# PCB-BI8-SE-C201.net
KiCad netlist of a schematic drawn in EAGLE
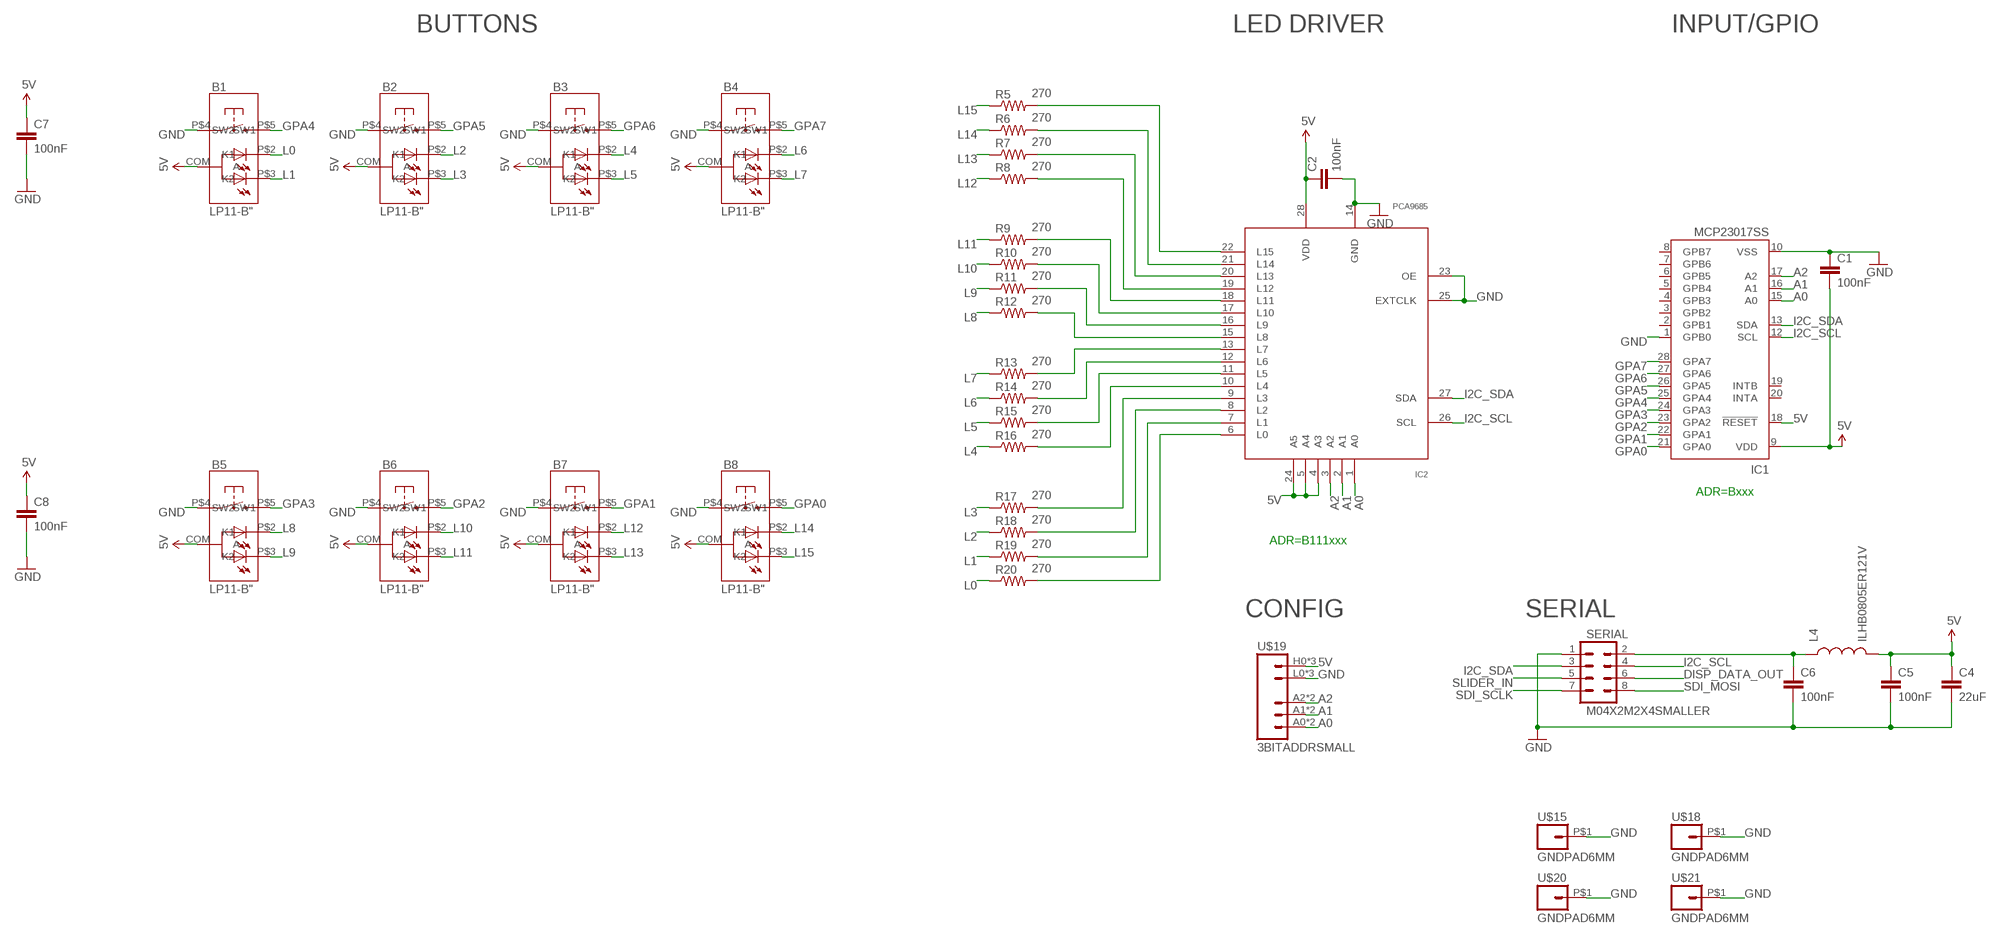
[diagram p0: schematic, sheet 1]

(export (version "E")
  (design (tool "Eeschema 10.0.6"))
  (components
    (comp (ref "B1")
      (value "LP11-B\"")
      (footprint "eagle-import:LP11")
      (libsource (lib "eagle-import") (part "LP11-B{dblquote}"))
    )
    (comp (ref "B2")
      (value "LP11-B\"")
      (footprint "eagle-import:LP11")
      (libsource (lib "eagle-import") (part "LP11-B{dblquote}"))
    )
    (comp (ref "B3")
      (value "LP11-B\"")
      (footprint "eagle-import:LP11")
      (libsource (lib "eagle-import") (part "LP11-B{dblquote}"))
    )
    (comp (ref "B4")
      (value "LP11-B\"")
      (footprint "eagle-import:LP11")
      (libsource (lib "eagle-import") (part "LP11-B{dblquote}"))
    )
    (comp (ref "B5")
      (value "LP11-B\"")
      (footprint "eagle-import:LP11")
      (libsource (lib "eagle-import") (part "LP11-B{dblquote}"))
    )
    (comp (ref "B6")
      (value "LP11-B\"")
      (footprint "eagle-import:LP11")
      (libsource (lib "eagle-import") (part "LP11-B{dblquote}"))
    )
    (comp (ref "B7")
      (value "LP11-B\"")
      (footprint "eagle-import:LP11")
      (libsource (lib "eagle-import") (part "LP11-B{dblquote}"))
    )
    (comp (ref "B8")
      (value "LP11-B\"")
      (footprint "eagle-import:LP11")
      (libsource (lib "eagle-import") (part "LP11-B{dblquote}"))
    )
    (comp (ref "C1")
      (value "100nF")
      (footprint "eagle-import:0603-CAP")
      (libsource (lib "eagle-import") (part "CAP0603-CAP"))
    )
    (comp (ref "C2")
      (value "100nF")
      (footprint "eagle-import:0603-CAP")
      (libsource (lib "eagle-import") (part "CAP0603-CAP"))
    )
    (comp (ref "C4")
      (value "22uF")
      (footprint "eagle-import:0805")
      (libsource (lib "eagle-import") (part "CAP0805"))
    )
    (comp (ref "C5")
      (value "100nF")
      (footprint "eagle-import:0603-CAP")
      (libsource (lib "eagle-import") (part "CAP0603-CAP"))
    )
    (comp (ref "C6")
      (value "100nF")
      (footprint "eagle-import:0603-CAP")
      (libsource (lib "eagle-import") (part "CAP0603-CAP"))
    )
    (comp (ref "C7")
      (value "100nF")
      (footprint "eagle-import:0603-CAP")
      (libsource (lib "eagle-import") (part "CAP0603-CAP"))
    )
    (comp (ref "C8")
      (value "100nF")
      (footprint "eagle-import:0603-CAP")
      (libsource (lib "eagle-import") (part "CAP0603-CAP"))
    )
    (comp (ref "IC1")
      (value "MCP23017SS")
      (footprint "eagle-import:SSOP28")
      (fields
        (field (name "MF") "MICROCHIP")
        (field (name "MPN") "MCP23017-E/SS")
        (field (name "MPN_1") "MCP23017-E/SS")
        (field (name "OC_FARNELL") "1467674")
        (field (name "OC_NEWARK") "31K2960")
      )
      (libsource (lib "eagle-import") (part "MCP23017SS"))
    )
    (comp (ref "IC2")
      (value "PCA9685")
      (footprint "eagle-import:TSSOP28")
      (libsource (lib "eagle-import") (part "PCA9685"))
    )
    (comp (ref "L4")
      (value "ILHB0805ER121V")
      (footprint "eagle-import:0805")
      (libsource (lib "eagle-import") (part "INDUCTOR0805"))
    )
    (comp (ref "R5")
      (value "270")
      (footprint "eagle-import:0603-RES")
      (libsource (lib "eagle-import") (part "RESISTOR0603-RES"))
    )
    (comp (ref "R6")
      (value "270")
      (footprint "eagle-import:0603-RES")
      (libsource (lib "eagle-import") (part "RESISTOR0603-RES"))
    )
    (comp (ref "R7")
      (value "270")
      (footprint "eagle-import:0603-RES")
      (libsource (lib "eagle-import") (part "RESISTOR0603-RES"))
    )
    (comp (ref "R8")
      (value "270")
      (footprint "eagle-import:0603-RES")
      (libsource (lib "eagle-import") (part "RESISTOR0603-RES"))
    )
    (comp (ref "R9")
      (value "270")
      (footprint "eagle-import:0603-RES")
      (libsource (lib "eagle-import") (part "RESISTOR0603-RES"))
    )
    (comp (ref "R10")
      (value "270")
      (footprint "eagle-import:0603-RES")
      (libsource (lib "eagle-import") (part "RESISTOR0603-RES"))
    )
    (comp (ref "R11")
      (value "270")
      (footprint "eagle-import:0603-RES")
      (libsource (lib "eagle-import") (part "RESISTOR0603-RES"))
    )
    (comp (ref "R12")
      (value "270")
      (footprint "eagle-import:0603-RES")
      (libsource (lib "eagle-import") (part "RESISTOR0603-RES"))
    )
    (comp (ref "R13")
      (value "270")
      (footprint "eagle-import:0603-RES")
      (libsource (lib "eagle-import") (part "RESISTOR0603-RES"))
    )
    (comp (ref "R14")
      (value "270")
      (footprint "eagle-import:0603-RES")
      (libsource (lib "eagle-import") (part "RESISTOR0603-RES"))
    )
    (comp (ref "R15")
      (value "270")
      (footprint "eagle-import:0603-RES")
      (libsource (lib "eagle-import") (part "RESISTOR0603-RES"))
    )
    (comp (ref "R16")
      (value "270")
      (footprint "eagle-import:0603-RES")
      (libsource (lib "eagle-import") (part "RESISTOR0603-RES"))
    )
    (comp (ref "R17")
      (value "270")
      (footprint "eagle-import:0603-RES")
      (libsource (lib "eagle-import") (part "RESISTOR0603-RES"))
    )
    (comp (ref "R18")
      (value "270")
      (footprint "eagle-import:0603-RES")
      (libsource (lib "eagle-import") (part "RESISTOR0603-RES"))
    )
    (comp (ref "R19")
      (value "270")
      (footprint "eagle-import:0603-RES")
      (libsource (lib "eagle-import") (part "RESISTOR0603-RES"))
    )
    (comp (ref "R20")
      (value "270")
      (footprint "eagle-import:0603-RES")
      (libsource (lib "eagle-import") (part "RESISTOR0603-RES"))
    )
    (comp (ref "SERIAL")
      (value "M04X2M2X4SMALLER")
      (footprint "eagle-import:M2X4SMALLER")
      (libsource (lib "eagle-import") (part "M04X2M2X4SMALLER"))
    )
    (comp (ref "U$15")
      (value "GNDPAD6MM")
      (footprint "eagle-import:3.2MMPAD6MM")
      (libsource (lib "eagle-import") (part "GNDPAD6MM"))
    )
    (comp (ref "U$18")
      (value "GNDPAD6MM")
      (footprint "eagle-import:3.2MMPAD6MM")
      (libsource (lib "eagle-import") (part "GNDPAD6MM"))
    )
    (comp (ref "U$19")
      (value "3BITADDRSMALL")
      (footprint "eagle-import:3BITADDR_SMALL")
      (libsource (lib "eagle-import") (part "3BITADDRSMALL"))
    )
    (comp (ref "U$20")
      (value "GNDPAD6MM")
      (footprint "eagle-import:3.2MMPAD6MM")
      (libsource (lib "eagle-import") (part "GNDPAD6MM"))
    )
    (comp (ref "U$21")
      (value "GNDPAD6MM")
      (footprint "eagle-import:3.2MMPAD6MM")
      (libsource (lib "eagle-import") (part "GNDPAD6MM"))
    )
  )
  (nets
    (net (code "1") (name "/A0") (class "Default")
      (node (ref "IC1") (pin "15") (pinfunction "A0_15") (pintype "input"))
      (node (ref "IC2") (pin "1") (pinfunction "A0_1") (pintype "input"))
      (node (ref "U$19") (pin "A0") (pinfunction "A0_A0") (pintype "passive"))
      (node (ref "U$19") (pin "AS0") (pinfunction "A0_AS0") (pintype "passive"))
    )
    (net (code "2") (name "/A1") (class "Default")
      (node (ref "IC1") (pin "16") (pinfunction "A1_16") (pintype "input"))
      (node (ref "IC2") (pin "2") (pinfunction "A1_2") (pintype "input"))
      (node (ref "U$19") (pin "A1") (pinfunction "A1_A1") (pintype "passive"))
      (node (ref "U$19") (pin "AS1") (pinfunction "A1_AS1") (pintype "passive"))
    )
    (net (code "3") (name "/A2") (class "Default")
      (node (ref "IC1") (pin "17") (pinfunction "A2_17") (pintype "input"))
      (node (ref "IC2") (pin "3") (pinfunction "A2_3") (pintype "input"))
      (node (ref "U$19") (pin "A2") (pinfunction "A2_A2") (pintype "passive"))
      (node (ref "U$19") (pin "AS2") (pinfunction "A2_AS2") (pintype "passive"))
    )
    (net (code "4") (name "/DISP_DATA_OUT") (class "Default")
      (node (ref "SERIAL") (pin "6") (pinfunction "6_6") (pintype "passive"))
    )
    (net (code "5") (name "/GPA0") (class "Default")
      (node (ref "B8") (pin "P$5") (pinfunction "SW2_P$5") (pintype "bidirectional"))
      (node (ref "IC1") (pin "21") (pinfunction "GPA0_21") (pintype "bidirectional"))
    )
    (net (code "6") (name "/GPA1") (class "Default")
      (node (ref "B7") (pin "P$5") (pinfunction "SW2_P$5") (pintype "bidirectional"))
      (node (ref "IC1") (pin "22") (pinfunction "GPA1_22") (pintype "bidirectional"))
    )
    (net (code "7") (name "/GPA2") (class "Default")
      (node (ref "B6") (pin "P$5") (pinfunction "SW2_P$5") (pintype "bidirectional"))
      (node (ref "IC1") (pin "23") (pinfunction "GPA2_23") (pintype "bidirectional"))
    )
    (net (code "8") (name "/GPA3") (class "Default")
      (node (ref "B5") (pin "P$5") (pinfunction "SW2_P$5") (pintype "bidirectional"))
      (node (ref "IC1") (pin "24") (pinfunction "GPA3_24") (pintype "bidirectional"))
    )
    (net (code "9") (name "/GPA4") (class "Default")
      (node (ref "B1") (pin "P$5") (pinfunction "SW2_P$5") (pintype "bidirectional"))
      (node (ref "IC1") (pin "25") (pinfunction "GPA4_25") (pintype "bidirectional"))
    )
    (net (code "10") (name "/GPA5") (class "Default")
      (node (ref "B2") (pin "P$5") (pinfunction "SW2_P$5") (pintype "bidirectional"))
      (node (ref "IC1") (pin "26") (pinfunction "GPA5_26") (pintype "bidirectional"))
    )
    (net (code "11") (name "/GPA6") (class "Default")
      (node (ref "B3") (pin "P$5") (pinfunction "SW2_P$5") (pintype "bidirectional"))
      (node (ref "IC1") (pin "27") (pinfunction "GPA6_27") (pintype "bidirectional"))
    )
    (net (code "12") (name "/GPA7") (class "Default")
      (node (ref "B4") (pin "P$5") (pinfunction "SW2_P$5") (pintype "bidirectional"))
      (node (ref "IC1") (pin "28") (pinfunction "GPA7_28") (pintype "bidirectional"))
    )
    (net (code "13") (name "/I2C_SCL") (class "Default")
      (node (ref "IC1") (pin "12") (pinfunction "SCL_12") (pintype "input"))
      (node (ref "IC2") (pin "26") (pinfunction "SCL_26") (pintype "input"))
      (node (ref "SERIAL") (pin "4") (pinfunction "4_4") (pintype "passive"))
    )
    (net (code "14") (name "/I2C_SDA") (class "Default")
      (node (ref "IC1") (pin "13") (pinfunction "SDA_13") (pintype "bidirectional"))
      (node (ref "IC2") (pin "27") (pinfunction "SDA_27") (pintype "input"))
      (node (ref "SERIAL") (pin "3") (pinfunction "3_3") (pintype "passive"))
    )
    (net (code "15") (name "/L0") (class "Default")
      (node (ref "B1") (pin "P$2") (pinfunction "K1_P$2") (pintype "bidirectional"))
      (node (ref "R20") (pin "1") (pinfunction "1_1") (pintype "passive"))
    )
    (net (code "16") (name "/L1") (class "Default")
      (node (ref "B1") (pin "P$3") (pinfunction "K2_P$3") (pintype "bidirectional"))
      (node (ref "R19") (pin "1") (pinfunction "1_1") (pintype "passive"))
    )
    (net (code "17") (name "/L2") (class "Default")
      (node (ref "B2") (pin "P$2") (pinfunction "K1_P$2") (pintype "bidirectional"))
      (node (ref "R18") (pin "1") (pinfunction "1_1") (pintype "passive"))
    )
    (net (code "18") (name "/L3") (class "Default")
      (node (ref "B2") (pin "P$3") (pinfunction "K2_P$3") (pintype "bidirectional"))
      (node (ref "R17") (pin "1") (pinfunction "1_1") (pintype "passive"))
    )
    (net (code "19") (name "/L4") (class "Default")
      (node (ref "B3") (pin "P$2") (pinfunction "K1_P$2") (pintype "bidirectional"))
      (node (ref "R16") (pin "1") (pinfunction "1_1") (pintype "passive"))
    )
    (net (code "20") (name "/L5") (class "Default")
      (node (ref "B3") (pin "P$3") (pinfunction "K2_P$3") (pintype "bidirectional"))
      (node (ref "R15") (pin "1") (pinfunction "1_1") (pintype "passive"))
    )
    (net (code "21") (name "/L6") (class "Default")
      (node (ref "B4") (pin "P$2") (pinfunction "K1_P$2") (pintype "bidirectional"))
      (node (ref "R14") (pin "1") (pinfunction "1_1") (pintype "passive"))
    )
    (net (code "22") (name "/L7") (class "Default")
      (node (ref "B4") (pin "P$3") (pinfunction "K2_P$3") (pintype "bidirectional"))
      (node (ref "R13") (pin "1") (pinfunction "1_1") (pintype "passive"))
    )
    (net (code "23") (name "/L8") (class "Default")
      (node (ref "B5") (pin "P$2") (pinfunction "K1_P$2") (pintype "bidirectional"))
      (node (ref "R12") (pin "1") (pinfunction "1_1") (pintype "passive"))
    )
    (net (code "24") (name "/L9") (class "Default")
      (node (ref "B5") (pin "P$3") (pinfunction "K2_P$3") (pintype "bidirectional"))
      (node (ref "R11") (pin "1") (pinfunction "1_1") (pintype "passive"))
    )
    (net (code "25") (name "/L10") (class "Default")
      (node (ref "B6") (pin "P$2") (pinfunction "K1_P$2") (pintype "bidirectional"))
      (node (ref "R10") (pin "1") (pinfunction "1_1") (pintype "passive"))
    )
    (net (code "26") (name "/L11") (class "Default")
      (node (ref "B6") (pin "P$3") (pinfunction "K2_P$3") (pintype "bidirectional"))
      (node (ref "R9") (pin "1") (pinfunction "1_1") (pintype "passive"))
    )
    (net (code "27") (name "/L12") (class "Default")
      (node (ref "B7") (pin "P$2") (pinfunction "K1_P$2") (pintype "bidirectional"))
      (node (ref "R8") (pin "1") (pinfunction "1_1") (pintype "passive"))
    )
    (net (code "28") (name "/L13") (class "Default")
      (node (ref "B7") (pin "P$3") (pinfunction "K2_P$3") (pintype "bidirectional"))
      (node (ref "R7") (pin "1") (pinfunction "1_1") (pintype "passive"))
    )
    (net (code "29") (name "/L14") (class "Default")
      (node (ref "B8") (pin "P$2") (pinfunction "K1_P$2") (pintype "bidirectional"))
      (node (ref "R6") (pin "1") (pinfunction "1_1") (pintype "passive"))
    )
    (net (code "30") (name "/L15") (class "Default")
      (node (ref "B8") (pin "P$3") (pinfunction "K2_P$3") (pintype "bidirectional"))
      (node (ref "R5") (pin "1") (pinfunction "1_1") (pintype "passive"))
    )
    (net (code "31") (name "/SDI_MOSI") (class "Default")
      (node (ref "SERIAL") (pin "8") (pinfunction "8_8") (pintype "passive"))
    )
    (net (code "32") (name "/SDI_SCLK") (class "Default")
      (node (ref "SERIAL") (pin "7") (pinfunction "7_7") (pintype "passive"))
    )
    (net (code "33") (name "/SLIDER_IN") (class "Default")
      (node (ref "SERIAL") (pin "5") (pinfunction "5_5") (pintype "passive"))
    )
    (net (code "34") (name "5V") (class "Default")
      (node (ref "B1") (pin "COM") (pinfunction "A_COM") (pintype "bidirectional"))
      (node (ref "B2") (pin "COM") (pinfunction "A_COM") (pintype "bidirectional"))
      (node (ref "B3") (pin "COM") (pinfunction "A_COM") (pintype "bidirectional"))
      (node (ref "B4") (pin "COM") (pinfunction "A_COM") (pintype "bidirectional"))
      (node (ref "B5") (pin "COM") (pinfunction "A_COM") (pintype "bidirectional"))
      (node (ref "B6") (pin "COM") (pinfunction "A_COM") (pintype "bidirectional"))
      (node (ref "B7") (pin "COM") (pinfunction "A_COM") (pintype "bidirectional"))
      (node (ref "B8") (pin "COM") (pinfunction "A_COM") (pintype "bidirectional"))
      (node (ref "C1") (pin "2") (pinfunction "2_2") (pintype "passive"))
      (node (ref "C2") (pin "1") (pinfunction "1_1") (pintype "passive"))
      (node (ref "C4") (pin "1") (pinfunction "1_1") (pintype "passive"))
      (node (ref "C5") (pin "1") (pinfunction "1_1") (pintype "passive"))
      (node (ref "C7") (pin "1") (pinfunction "1_1") (pintype "passive"))
      (node (ref "C8") (pin "1") (pinfunction "1_1") (pintype "passive"))
      (node (ref "IC1") (pin "18") (pinfunction "~{RESET}_18") (pintype "input"))
      (node (ref "IC1") (pin "9") (pinfunction "VDD_9") (pintype "power_in"))
      (node (ref "IC2") (pin "24") (pinfunction "A5_24") (pintype "input"))
      (node (ref "IC2") (pin "28") (pinfunction "VDD_28") (pintype "power_in"))
      (node (ref "IC2") (pin "4") (pinfunction "A3_4") (pintype "input"))
      (node (ref "IC2") (pin "5") (pinfunction "A4_5") (pintype "input"))
      (node (ref "L4") (pin "2") (pinfunction "2_2") (pintype "passive"))
      (node (ref "U$19") (pin "H0") (pinfunction "VCC_H0") (pintype "passive"))
      (node (ref "U$19") (pin "H1") (pinfunction "VCC_H1") (pintype "passive"))
      (node (ref "U$19") (pin "H2") (pinfunction "VCC_H2") (pintype "passive"))
    )
    (net (code "35") (name "GND") (class "Default")
      (node (ref "B1") (pin "P$4") (pinfunction "SW1_P$4") (pintype "bidirectional"))
      (node (ref "B2") (pin "P$4") (pinfunction "SW1_P$4") (pintype "bidirectional"))
      (node (ref "B3") (pin "P$4") (pinfunction "SW1_P$4") (pintype "bidirectional"))
      (node (ref "B4") (pin "P$4") (pinfunction "SW1_P$4") (pintype "bidirectional"))
      (node (ref "B5") (pin "P$4") (pinfunction "SW1_P$4") (pintype "bidirectional"))
      (node (ref "B6") (pin "P$4") (pinfunction "SW1_P$4") (pintype "bidirectional"))
      (node (ref "B7") (pin "P$4") (pinfunction "SW1_P$4") (pintype "bidirectional"))
      (node (ref "B8") (pin "P$4") (pinfunction "SW1_P$4") (pintype "bidirectional"))
      (node (ref "C1") (pin "1") (pinfunction "1_1") (pintype "passive"))
      (node (ref "C2") (pin "2") (pinfunction "2_2") (pintype "passive"))
      (node (ref "C4") (pin "2") (pinfunction "2_2") (pintype "passive"))
      (node (ref "C5") (pin "2") (pinfunction "2_2") (pintype "passive"))
      (node (ref "C6") (pin "2") (pinfunction "2_2") (pintype "passive"))
      (node (ref "C7") (pin "2") (pinfunction "2_2") (pintype "passive"))
      (node (ref "C8") (pin "2") (pinfunction "2_2") (pintype "passive"))
      (node (ref "IC1") (pin "1") (pinfunction "GPB0_1") (pintype "bidirectional"))
      (node (ref "IC1") (pin "10") (pinfunction "VSS_10") (pintype "power_in"))
      (node (ref "IC2") (pin "14") (pinfunction "GND_14") (pintype "power_in"))
      (node (ref "IC2") (pin "23") (pinfunction "OE_23") (pintype "input"))
      (node (ref "IC2") (pin "25") (pinfunction "EXTCLK_25") (pintype "input"))
      (node (ref "SERIAL") (pin "1") (pinfunction "1_1") (pintype "passive"))
      (node (ref "U$15") (pin "P$1") (pinfunction "1_P$1") (pintype "passive"))
      (node (ref "U$18") (pin "P$1") (pinfunction "1_P$1") (pintype "passive"))
      (node (ref "U$19") (pin "L0") (pinfunction "GND_L0") (pintype "passive"))
      (node (ref "U$19") (pin "L1") (pinfunction "GND_L1") (pintype "passive"))
      (node (ref "U$19") (pin "L2") (pinfunction "GND_L2") (pintype "passive"))
      (node (ref "U$20") (pin "P$1") (pinfunction "1_P$1") (pintype "passive"))
      (node (ref "U$21") (pin "P$1") (pinfunction "1_P$1") (pintype "passive"))
    )
    (net (code "36") (name "Net-(C6-Pad1)") (class "Default")
      (node (ref "C6") (pin "1") (pinfunction "1_1") (pintype "passive"))
      (node (ref "L4") (pin "1") (pinfunction "1_1") (pintype "passive"))
      (node (ref "SERIAL") (pin "2") (pinfunction "2_2") (pintype "passive"))
    )
    (net (code "37") (name "Net-(IC2-L0)") (class "Default")
      (node (ref "IC2") (pin "6") (pinfunction "L0_6") (pintype "output"))
      (node (ref "R20") (pin "2") (pinfunction "2_2") (pintype "passive"))
    )
    (net (code "38") (name "Net-(IC2-L1)") (class "Default")
      (node (ref "IC2") (pin "7") (pinfunction "L1_7") (pintype "output"))
      (node (ref "R19") (pin "2") (pinfunction "2_2") (pintype "passive"))
    )
    (net (code "39") (name "Net-(IC2-L2)") (class "Default")
      (node (ref "IC2") (pin "8") (pinfunction "L2_8") (pintype "output"))
      (node (ref "R18") (pin "2") (pinfunction "2_2") (pintype "passive"))
    )
    (net (code "40") (name "Net-(IC2-L3)") (class "Default")
      (node (ref "IC2") (pin "9") (pinfunction "L3_9") (pintype "output"))
      (node (ref "R17") (pin "2") (pinfunction "2_2") (pintype "passive"))
    )
    (net (code "41") (name "Net-(IC2-L4)") (class "Default")
      (node (ref "IC2") (pin "10") (pinfunction "L4_10") (pintype "output"))
      (node (ref "R16") (pin "2") (pinfunction "2_2") (pintype "passive"))
    )
    (net (code "42") (name "Net-(IC2-L5)") (class "Default")
      (node (ref "IC2") (pin "11") (pinfunction "L5_11") (pintype "output"))
      (node (ref "R15") (pin "2") (pinfunction "2_2") (pintype "passive"))
    )
    (net (code "43") (name "Net-(IC2-L6)") (class "Default")
      (node (ref "IC2") (pin "12") (pinfunction "L6_12") (pintype "output"))
      (node (ref "R14") (pin "2") (pinfunction "2_2") (pintype "passive"))
    )
    (net (code "44") (name "Net-(IC2-L7)") (class "Default")
      (node (ref "IC2") (pin "13") (pinfunction "L7_13") (pintype "output"))
      (node (ref "R13") (pin "2") (pinfunction "2_2") (pintype "passive"))
    )
    (net (code "45") (name "Net-(IC2-L8)") (class "Default")
      (node (ref "IC2") (pin "15") (pinfunction "L8_15") (pintype "output"))
      (node (ref "R12") (pin "2") (pinfunction "2_2") (pintype "passive"))
    )
    (net (code "46") (name "Net-(IC2-L9)") (class "Default")
      (node (ref "IC2") (pin "16") (pinfunction "L9_16") (pintype "output"))
      (node (ref "R11") (pin "2") (pinfunction "2_2") (pintype "passive"))
    )
    (net (code "47") (name "Net-(IC2-L10)") (class "Default")
      (node (ref "IC2") (pin "17") (pinfunction "L10_17") (pintype "output"))
      (node (ref "R10") (pin "2") (pinfunction "2_2") (pintype "passive"))
    )
    (net (code "48") (name "Net-(IC2-L11)") (class "Default")
      (node (ref "IC2") (pin "18") (pinfunction "L11_18") (pintype "output"))
      (node (ref "R9") (pin "2") (pinfunction "2_2") (pintype "passive"))
    )
    (net (code "49") (name "Net-(IC2-L12)") (class "Default")
      (node (ref "IC2") (pin "19") (pinfunction "L12_19") (pintype "output"))
      (node (ref "R8") (pin "2") (pinfunction "2_2") (pintype "passive"))
    )
    (net (code "50") (name "Net-(IC2-L13)") (class "Default")
      (node (ref "IC2") (pin "20") (pinfunction "L13_20") (pintype "output"))
      (node (ref "R7") (pin "2") (pinfunction "2_2") (pintype "passive"))
    )
    (net (code "51") (name "Net-(IC2-L14)") (class "Default")
      (node (ref "IC2") (pin "21") (pinfunction "L14_21") (pintype "output"))
      (node (ref "R6") (pin "2") (pinfunction "2_2") (pintype "passive"))
    )
    (net (code "52") (name "Net-(IC2-L15)") (class "Default")
      (node (ref "IC2") (pin "22") (pinfunction "L15_22") (pintype "output"))
      (node (ref "R5") (pin "2") (pinfunction "2_2") (pintype "passive"))
    )
    (net (code "53") (name "unconnected-(IC1-GPB1-Pad2)") (class "Default")
      (node (ref "IC1") (pin "2") (pinfunction "GPB1_2") (pintype "bidirectional"))
    )
    (net (code "54") (name "unconnected-(IC1-GPB2-Pad3)") (class "Default")
      (node (ref "IC1") (pin "3") (pinfunction "GPB2_3") (pintype "bidirectional"))
    )
    (net (code "55") (name "unconnected-(IC1-GPB3-Pad4)") (class "Default")
      (node (ref "IC1") (pin "4") (pinfunction "GPB3_4") (pintype "bidirectional"))
    )
    (net (code "56") (name "unconnected-(IC1-GPB4-Pad5)") (class "Default")
      (node (ref "IC1") (pin "5") (pinfunction "GPB4_5") (pintype "bidirectional"))
    )
    (net (code "57") (name "unconnected-(IC1-GPB5-Pad6)") (class "Default")
      (node (ref "IC1") (pin "6") (pinfunction "GPB5_6") (pintype "bidirectional"))
    )
    (net (code "58") (name "unconnected-(IC1-GPB6-Pad7)") (class "Default")
      (node (ref "IC1") (pin "7") (pinfunction "GPB6_7") (pintype "bidirectional"))
    )
    (net (code "59") (name "unconnected-(IC1-GPB7-Pad8)") (class "Default")
      (node (ref "IC1") (pin "8") (pinfunction "GPB7_8") (pintype "bidirectional"))
    )
    (net (code "60") (name "unconnected-(IC1-INTA-Pad20)") (class "Default")
      (node (ref "IC1") (pin "20") (pinfunction "INTA_20") (pintype "output"))
    )
    (net (code "61") (name "unconnected-(IC1-INTB-Pad19)") (class "Default")
      (node (ref "IC1") (pin "19") (pinfunction "INTB_19") (pintype "output"))
    )
  )
)
